# working.net
KiCad netlist of a schematic drawn in EAGLE
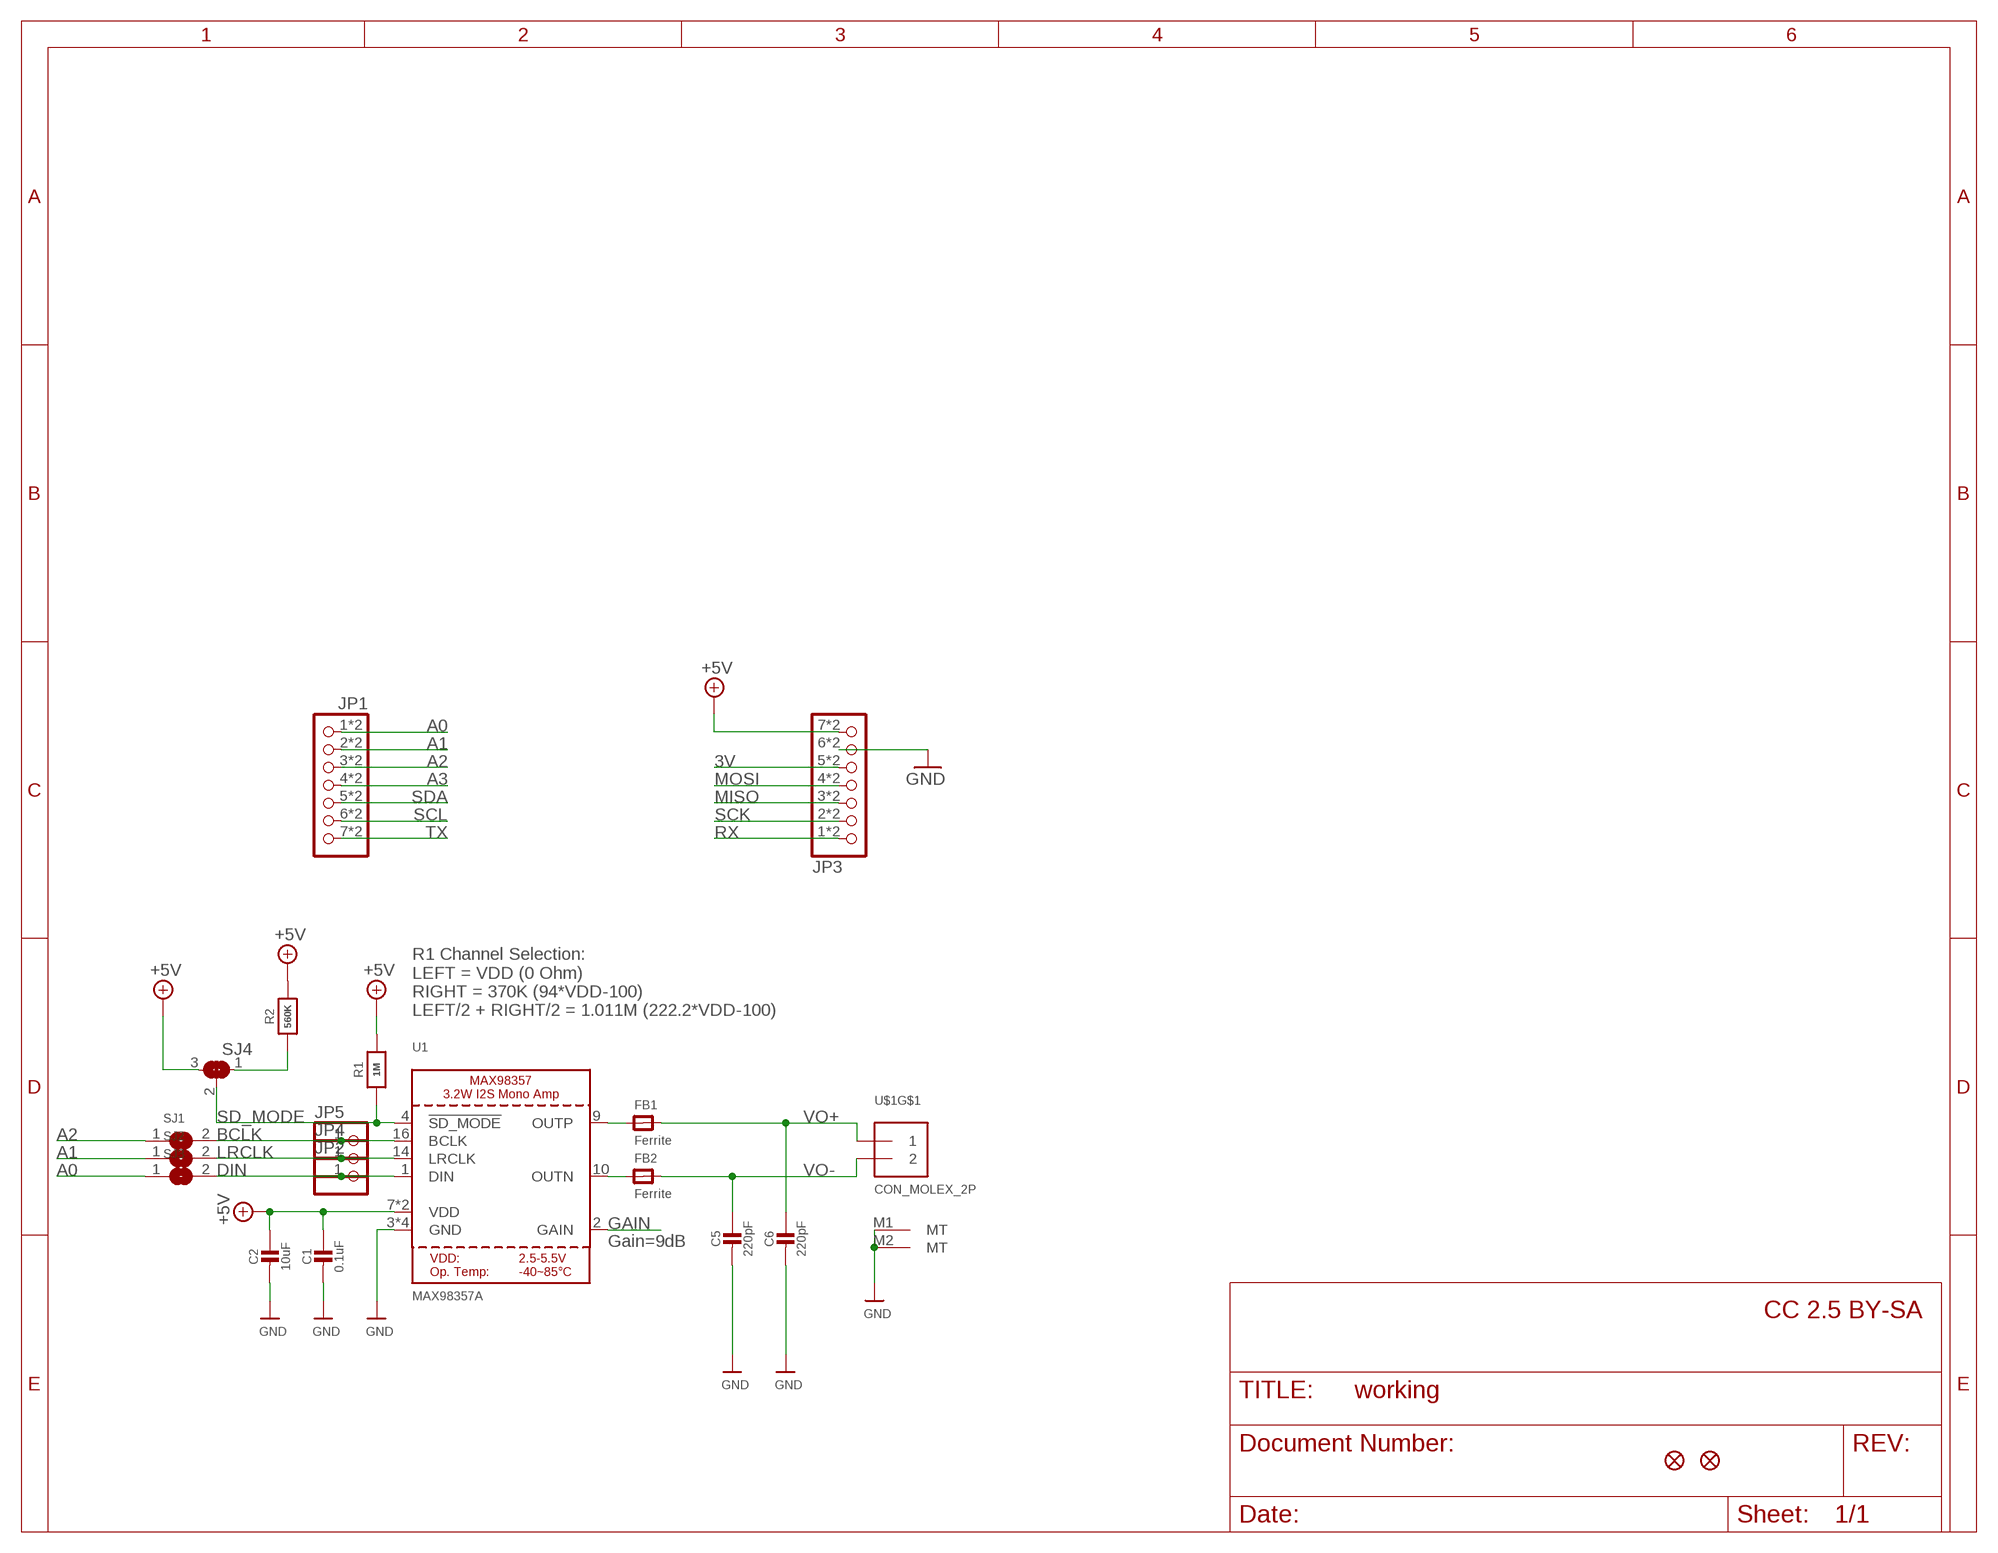
[diagram p0: schematic, sheet 1]

(export (version "E")
  (design (tool "Eeschema 10.0.6"))
  (components
    (comp (ref "C1")
      (value "0.1uF")
      (footprint "eagle-import:0603-NO")
      (libsource (lib "eagle-import") (part "CAP_CERAMIC0603_NO"))
    )
    (comp (ref "C2")
      (value "10uF")
      (footprint "eagle-import:0805-NO")
      (libsource (lib "eagle-import") (part "CAP_CERAMIC0805-NOOUTLINE"))
    )
    (comp (ref "C5")
      (value "220pF")
      (footprint "eagle-import:0603-NO")
      (libsource (lib "eagle-import") (part "CAP_CERAMIC0603_NO"))
    )
    (comp (ref "C6")
      (value "220pF")
      (footprint "eagle-import:0603-NO")
      (libsource (lib "eagle-import") (part "CAP_CERAMIC0603_NO"))
    )
    (comp (ref "FB1")
      (value "Ferrite")
      (footprint "eagle-import:0603-NO")
      (libsource (lib "eagle-import") (part "FERRITE-0603NO"))
    )
    (comp (ref "FB2")
      (value "Ferrite")
      (footprint "eagle-import:0603-NO")
      (libsource (lib "eagle-import") (part "FERRITE-0603NO"))
    )
    (comp (ref "JP1")
      (value "HEADER-1X7_CASTEL")
      (footprint "eagle-import:1X07_CASTEL")
      (libsource (lib "eagle-import") (part "HEADER-1X7_CASTEL"))
    )
    (comp (ref "JP2")
      (value "HEADER-1X12MM")
      (footprint "eagle-import:1X01_2MM")
      (libsource (lib "eagle-import") (part "HEADER-1X12MM"))
    )
    (comp (ref "JP3")
      (value "HEADER-1X7_CASTEL")
      (footprint "eagle-import:1X07_CASTEL")
      (libsource (lib "eagle-import") (part "HEADER-1X7_CASTEL"))
    )
    (comp (ref "JP4")
      (value "HEADER-1X12MM")
      (footprint "eagle-import:1X01_2MM")
      (libsource (lib "eagle-import") (part "HEADER-1X12MM"))
    )
    (comp (ref "JP5")
      (value "HEADER-1X12MM")
      (footprint "eagle-import:1X01_2MM")
      (libsource (lib "eagle-import") (part "HEADER-1X12MM"))
    )
    (comp (ref "R1")
      (value "1M")
      (footprint "eagle-import:0603-NO")
      (libsource (lib "eagle-import") (part "RESISTOR_0603_NOOUT"))
    )
    (comp (ref "R2")
      (value "560K")
      (footprint "eagle-import:0603-NO")
      (libsource (lib "eagle-import") (part "RESISTOR_0603_NOOUT"))
    )
    (comp (ref "SJ1")
      (value "SOLDERJUMPERCLOSED")
      (footprint "eagle-import:SOLDERJUMPER_CLOSEDWIRE")
      (libsource (lib "eagle-import") (part "SOLDERJUMPERCLOSED"))
    )
    (comp (ref "SJ2")
      (value "SOLDERJUMPERCLOSED")
      (footprint "eagle-import:SOLDERJUMPER_CLOSEDWIRE")
      (libsource (lib "eagle-import") (part "SOLDERJUMPERCLOSED"))
    )
    (comp (ref "SJ3")
      (value "SOLDERJUMPERCLOSED")
      (footprint "eagle-import:SOLDERJUMPER_CLOSEDWIRE")
      (libsource (lib "eagle-import") (part "SOLDERJUMPERCLOSED"))
    )
    (comp (ref "SJ4")
      (value "SOLDERJUMPER_2WAY")
      (footprint "eagle-import:SOLDERJUMPER_2WAY_OPEN_NOPASTE")
      (libsource (lib "eagle-import") (part "SOLDERJUMPER_2WAY"))
    )
    (comp (ref "U$1")
      (value "CON_MOLEX_2P")
      (footprint "eagle-import:53398-0271")
      (libsource (lib "eagle-import") (part "CON_MOLEX_2P"))
    )
    (comp (ref "U$6")
      (value "FIDUCIAL_1MM")
      (footprint "eagle-import:FIDUCIAL_1MM")
      (libsource (lib "eagle-import") (part "FIDUCIAL_1MM"))
    )
    (comp (ref "U$8")
      (value "FIDUCIAL_1MM")
      (footprint "eagle-import:FIDUCIAL_1MM")
      (libsource (lib "eagle-import") (part "FIDUCIAL_1MM"))
    )
    (comp (ref "U1")
      (value "MAX98357A")
      (footprint "eagle-import:QFN16_3MM")
      (libsource (lib "eagle-import") (part "AUDIOAMP_MAX98357"))
    )
  )
  (nets
    (net (code "1") (name "+5V") (class "Default")
      (node (ref "C1") (pin "1") (pinfunction "1_1") (pintype "passive"))
      (node (ref "C2") (pin "1") (pinfunction "1_1") (pintype "passive"))
      (node (ref "JP3") (pin "7") (pinfunction "7_7") (pintype "passive"))
      (node (ref "JP3") (pin "7C") (pinfunction "7_7C") (pintype "passive"))
      (node (ref "R1") (pin "2") (pinfunction "2_2") (pintype "passive"))
      (node (ref "R2") (pin "2") (pinfunction "2_2") (pintype "passive"))
      (node (ref "SJ4") (pin "3") (pinfunction "3_3") (pintype "passive"))
      (node (ref "U1") (pin "7") (pinfunction "VDD_7") (pintype "power_in"))
      (node (ref "U1") (pin "8") (pinfunction "VDD_8") (pintype "power_in"))
    )
    (net (code "2") (name "/3V") (class "Default")
      (node (ref "JP3") (pin "5") (pinfunction "5_5") (pintype "passive"))
      (node (ref "JP3") (pin "5C") (pinfunction "5_5C") (pintype "passive"))
    )
    (net (code "3") (name "/A0") (class "Default")
      (node (ref "JP1") (pin "1") (pinfunction "1_1") (pintype "passive"))
      (node (ref "JP1") (pin "1C") (pinfunction "1_1C") (pintype "passive"))
      (node (ref "SJ3") (pin "1") (pinfunction "1_1") (pintype "passive"))
    )
    (net (code "4") (name "/A1") (class "Default")
      (node (ref "JP1") (pin "2") (pinfunction "2_2") (pintype "passive"))
      (node (ref "JP1") (pin "2C") (pinfunction "2_2C") (pintype "passive"))
      (node (ref "SJ2") (pin "1") (pinfunction "1_1") (pintype "passive"))
    )
    (net (code "5") (name "/A2") (class "Default")
      (node (ref "JP1") (pin "3") (pinfunction "3_3") (pintype "passive"))
      (node (ref "JP1") (pin "3C") (pinfunction "3_3C") (pintype "passive"))
      (node (ref "SJ1") (pin "1") (pinfunction "1_1") (pintype "passive"))
    )
    (net (code "6") (name "/A3") (class "Default")
      (node (ref "JP1") (pin "4") (pinfunction "4_4") (pintype "passive"))
      (node (ref "JP1") (pin "4C") (pinfunction "4_4C") (pintype "passive"))
    )
    (net (code "7") (name "/BCLK") (class "Default")
      (node (ref "JP5") (pin "1") (pinfunction "1_1") (pintype "passive"))
      (node (ref "SJ1") (pin "2") (pinfunction "2_2") (pintype "passive"))
      (node (ref "U1") (pin "16") (pinfunction "BCLK_16") (pintype "bidirectional"))
    )
    (net (code "8") (name "/DIN") (class "Default")
      (node (ref "JP2") (pin "1") (pinfunction "1_1") (pintype "passive"))
      (node (ref "SJ3") (pin "2") (pinfunction "2_2") (pintype "passive"))
      (node (ref "U1") (pin "1") (pinfunction "DIN_1") (pintype "bidirectional"))
    )
    (net (code "9") (name "/GAIN") (class "Default")
      (node (ref "U1") (pin "2") (pinfunction "GAIN_2") (pintype "bidirectional"))
    )
    (net (code "10") (name "/LRCLK") (class "Default")
      (node (ref "JP4") (pin "1") (pinfunction "1_1") (pintype "passive"))
      (node (ref "SJ2") (pin "2") (pinfunction "2_2") (pintype "passive"))
      (node (ref "U1") (pin "14") (pinfunction "LRCLK_14") (pintype "bidirectional"))
    )
    (net (code "11") (name "/MISO") (class "Default")
      (node (ref "JP3") (pin "3") (pinfunction "3_3") (pintype "passive"))
      (node (ref "JP3") (pin "3C") (pinfunction "3_3C") (pintype "passive"))
    )
    (net (code "12") (name "/MOSI") (class "Default")
      (node (ref "JP3") (pin "4") (pinfunction "4_4") (pintype "passive"))
      (node (ref "JP3") (pin "4C") (pinfunction "4_4C") (pintype "passive"))
    )
    (net (code "13") (name "/RX") (class "Default")
      (node (ref "JP3") (pin "1") (pinfunction "1_1") (pintype "passive"))
      (node (ref "JP3") (pin "1C") (pinfunction "1_1C") (pintype "passive"))
    )
    (net (code "14") (name "/SCK") (class "Default")
      (node (ref "JP3") (pin "2") (pinfunction "2_2") (pintype "passive"))
      (node (ref "JP3") (pin "2C") (pinfunction "2_2C") (pintype "passive"))
    )
    (net (code "15") (name "/SCL") (class "Default")
      (node (ref "JP1") (pin "6") (pinfunction "6_6") (pintype "passive"))
      (node (ref "JP1") (pin "6C") (pinfunction "6_6C") (pintype "passive"))
    )
    (net (code "16") (name "/SDA") (class "Default")
      (node (ref "JP1") (pin "5") (pinfunction "5_5") (pintype "passive"))
      (node (ref "JP1") (pin "5C") (pinfunction "5_5C") (pintype "passive"))
    )
    (net (code "17") (name "/SD_MODE") (class "Default")
      (node (ref "R1") (pin "1") (pinfunction "1_1") (pintype "passive"))
      (node (ref "SJ4") (pin "2") (pinfunction "2_2") (pintype "passive"))
      (node (ref "U1") (pin "4") (pinfunction "~{SD_MODE}_4") (pintype "bidirectional"))
    )
    (net (code "18") (name "/TX") (class "Default")
      (node (ref "JP1") (pin "7") (pinfunction "7_7") (pintype "passive"))
      (node (ref "JP1") (pin "7C") (pinfunction "7_7C") (pintype "passive"))
    )
    (net (code "19") (name "/VO+") (class "Default")
      (node (ref "C6") (pin "1") (pinfunction "1_1") (pintype "passive"))
      (node (ref "FB1") (pin "2") (pinfunction "P$2_2") (pintype "passive"))
      (node (ref "U$1") (pin "1") (pinfunction "1_1") (pintype "passive"))
    )
    (net (code "20") (name "/VO-") (class "Default")
      (node (ref "C5") (pin "1") (pinfunction "1_1") (pintype "passive"))
      (node (ref "FB2") (pin "2") (pinfunction "P$2_2") (pintype "passive"))
      (node (ref "U$1") (pin "2") (pinfunction "2_2") (pintype "passive"))
    )
    (net (code "21") (name "GND") (class "Default")
      (node (ref "C1") (pin "2") (pinfunction "2_2") (pintype "passive"))
      (node (ref "C2") (pin "2") (pinfunction "2_2") (pintype "passive"))
      (node (ref "C5") (pin "2") (pinfunction "2_2") (pintype "passive"))
      (node (ref "C6") (pin "2") (pinfunction "2_2") (pintype "passive"))
      (node (ref "JP3") (pin "6") (pinfunction "6_6") (pintype "passive"))
      (node (ref "JP3") (pin "6C") (pinfunction "6_6C") (pintype "passive"))
      (node (ref "U$1") (pin "M1") (pinfunction "MT_M1") (pintype "bidirectional"))
      (node (ref "U$1") (pin "M2") (pinfunction "MT_M2") (pintype "bidirectional"))
      (node (ref "U1") (pin "11") (pinfunction "GND_11") (pintype "power_in"))
      (node (ref "U1") (pin "15") (pinfunction "GND_15") (pintype "power_in"))
      (node (ref "U1") (pin "3") (pinfunction "GND_3") (pintype "power_in"))
      (node (ref "U1") (pin "THERMAL") (pinfunction "GND_THERMAL") (pintype "power_in"))
    )
    (net (code "22") (name "Net-(FB1-P$1)") (class "Default")
      (node (ref "FB1") (pin "1") (pinfunction "P$1_1") (pintype "passive"))
      (node (ref "U1") (pin "9") (pinfunction "OUTP_9") (pintype "output"))
    )
    (net (code "23") (name "Net-(FB2-P$1)") (class "Default")
      (node (ref "FB2") (pin "1") (pinfunction "P$1_1") (pintype "passive"))
      (node (ref "U1") (pin "10") (pinfunction "OUTN_10") (pintype "output"))
    )
    (net (code "24") (name "Net-(R2-Pad1)") (class "Default")
      (node (ref "R2") (pin "1") (pinfunction "1_1") (pintype "passive"))
      (node (ref "SJ4") (pin "1") (pinfunction "1_1") (pintype "passive"))
    )
  )
)
